# Counter_Display_v2.net
KiCad netlist of a schematic drawn in Altium Designer
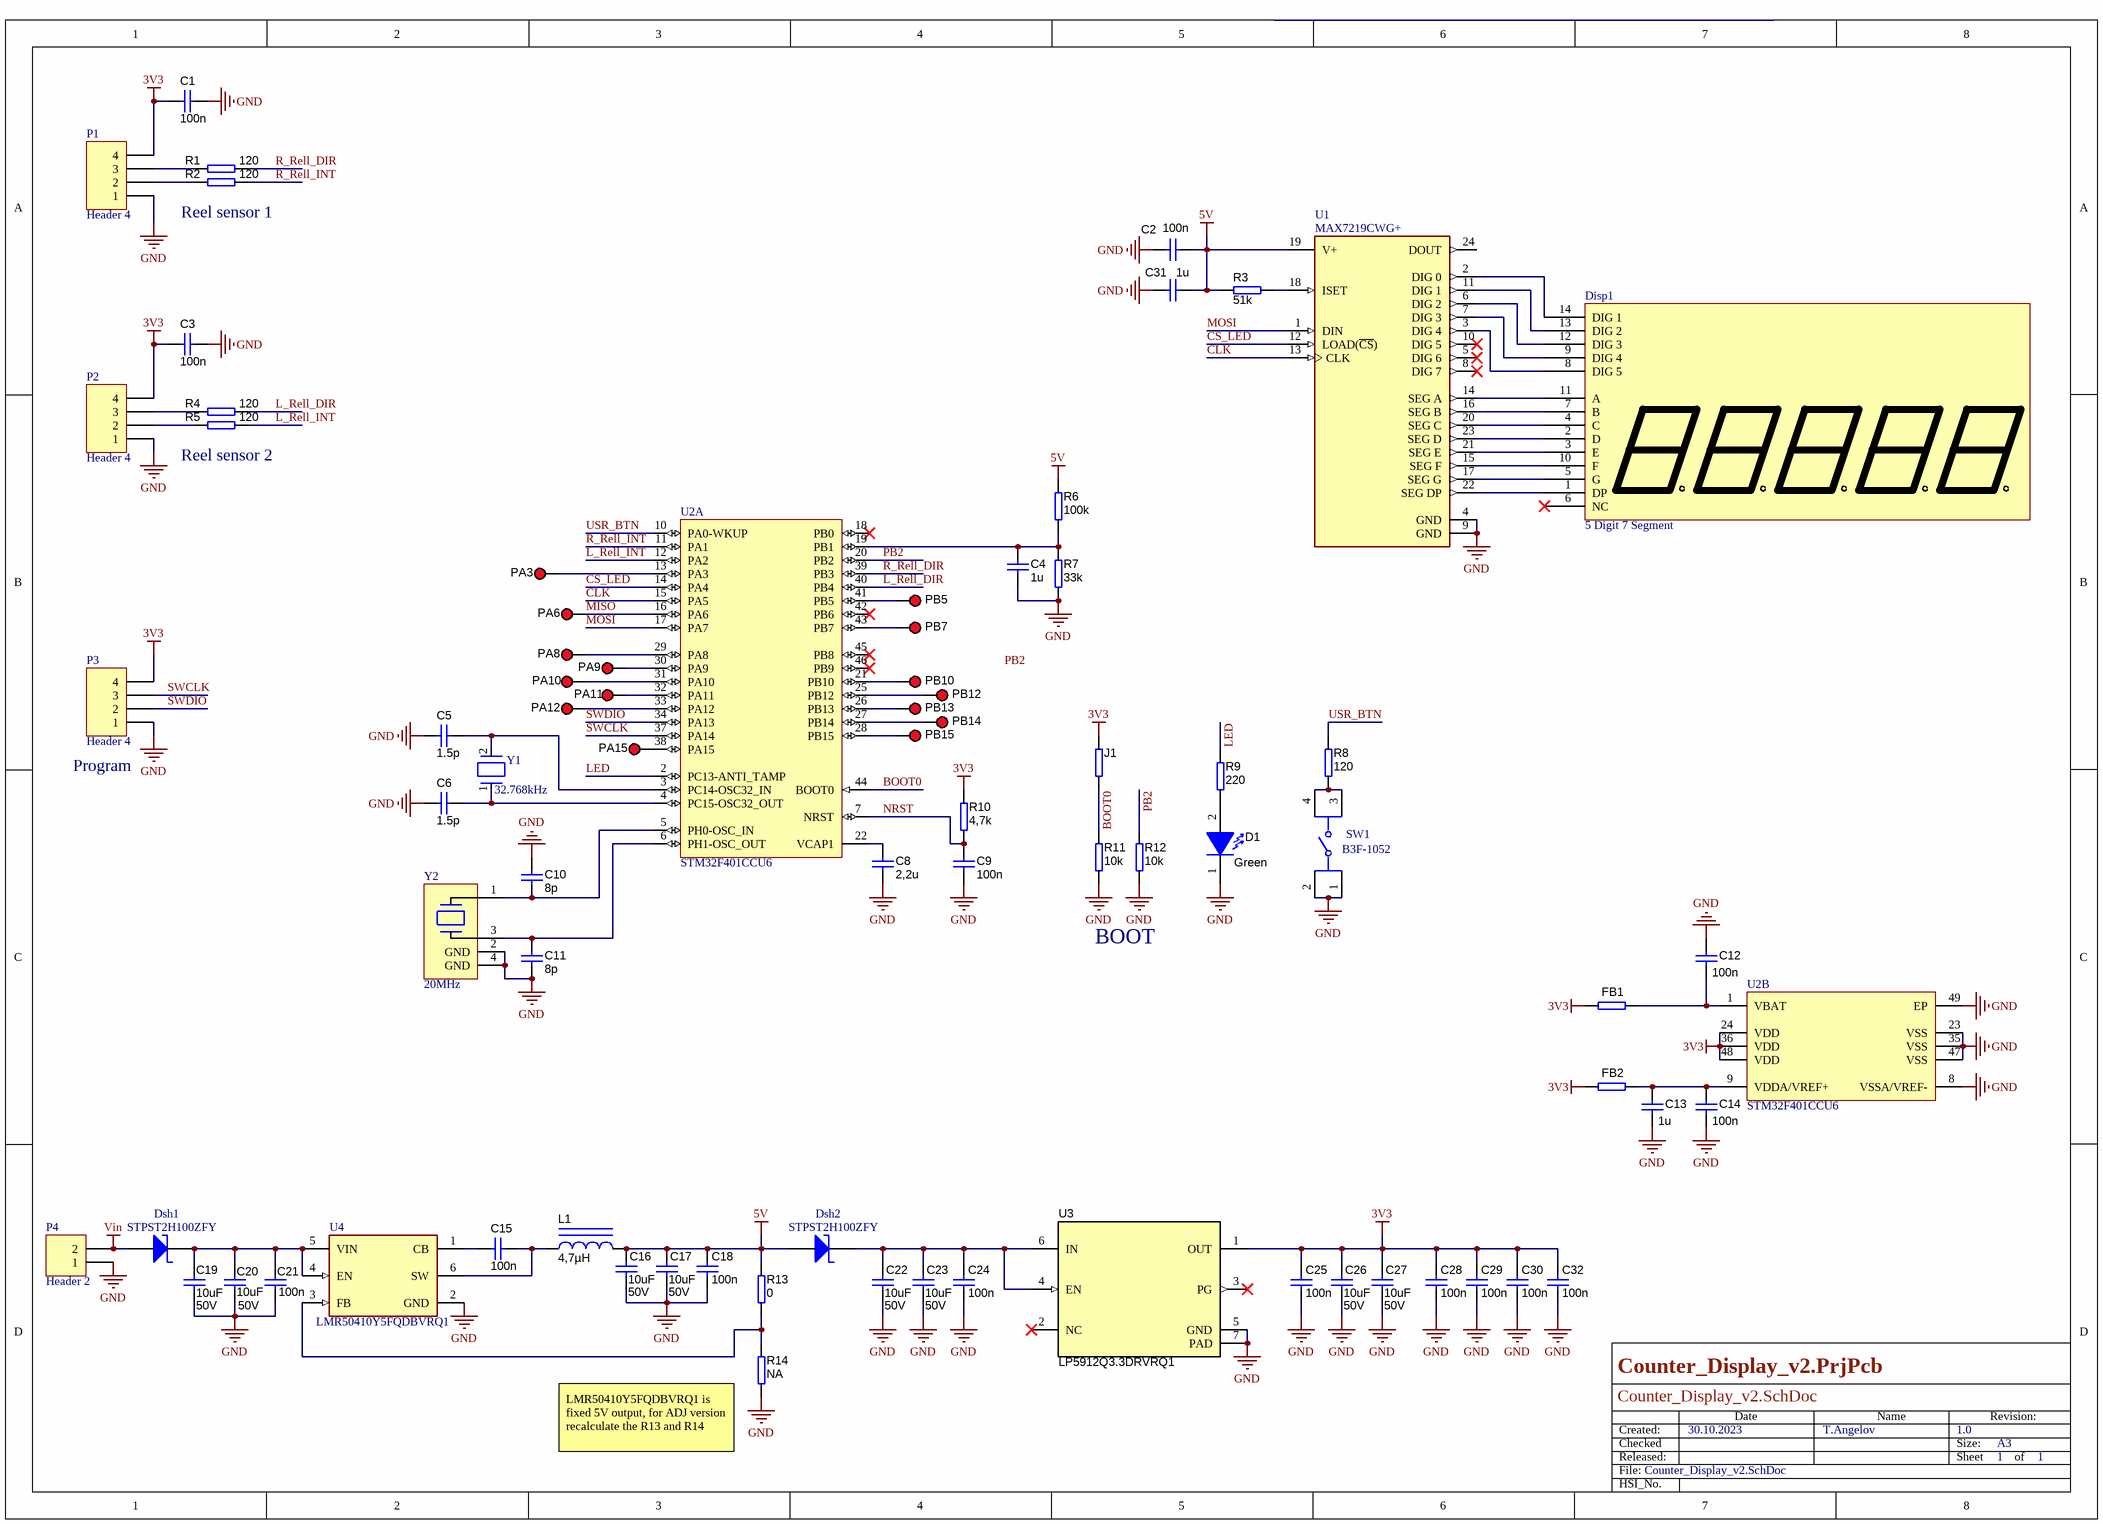
[diagram p0: Counter_Display_v2.SchDoc]

(export (version "E")
  (design (tool "Eeschema 10.0.6"))
  (components
    (comp (ref "C1")
      (value "100n")
      (footprint "0805_HV")
      (description "CAP, CERM, +/- 10%, X7S,  0805")
      (libsource (lib "Const_Cur_Source") (part "C0805"))
    )
    (comp (ref "C2")
      (value "100n")
      (footprint "0805_HV")
      (description "CAP, CERM, +/- 10%, X7S,  0805")
      (libsource (lib "Const_Cur_Source") (part "C0805"))
    )
    (comp (ref "C3")
      (value "100n")
      (footprint "0805_HV")
      (description "CAP, CERM, +/- 10%, X7S,  0805")
      (libsource (lib "Const_Cur_Source") (part "C0805"))
    )
    (comp (ref "C4")
      (value "1u")
      (footprint "0805_HV")
      (description "CAP, CERM, +/- 10%, X7S,  0805")
      (libsource (lib "Const_Cur_Source") (part "C0805"))
    )
    (comp (ref "C5")
      (value "1.5p")
      (footprint "0805_HV")
      (description "CAP, CERM, +/- 10%, X7S,  0805")
      (libsource (lib "Const_Cur_Source") (part "C0805"))
    )
    (comp (ref "C6")
      (value "1.5p")
      (footprint "0805_HV")
      (description "CAP, CERM, +/- 10%, X7S,  0805")
      (libsource (lib "Const_Cur_Source") (part "C0805"))
    )
    (comp (ref "C8")
      (value "2,2u")
      (footprint "0805_HV")
      (description "CAP, CERM, +/- 10%, X7S,  0805")
      (libsource (lib "Const_Cur_Source") (part "C0805"))
    )
    (comp (ref "C9")
      (value "100n")
      (footprint "0805_HV")
      (description "CAP, CERM, +/- 10%, X7S,  0805")
      (libsource (lib "Const_Cur_Source") (part "C0805"))
    )
    (comp (ref "C10")
      (value "8p")
      (footprint "0805_HV")
      (description "CAP, CERM, +/- 10%, X7S,  0805")
      (libsource (lib "Const_Cur_Source") (part "C0805"))
    )
    (comp (ref "C11")
      (value "8p")
      (footprint "0805_HV")
      (description "CAP, CERM, +/- 10%, X7S,  0805")
      (libsource (lib "Const_Cur_Source") (part "C0805"))
    )
    (comp (ref "C12")
      (value "100n")
      (footprint "0805_HV")
      (description "CAP, CERM, +/- 10%, X7S,  0805")
      (libsource (lib "Const_Cur_Source") (part "C0805"))
    )
    (comp (ref "C13")
      (value "1u")
      (footprint "0805_HV")
      (description "CAP, CERM, +/- 10%, X7S,  0805")
      (libsource (lib "Const_Cur_Source") (part "C0805"))
    )
    (comp (ref "C14")
      (value "100n")
      (footprint "0805_HV")
      (description "CAP, CERM, +/- 10%, X7S,  0805")
      (libsource (lib "Const_Cur_Source") (part "C0805"))
    )
    (comp (ref "C15")
      (value "100n")
      (footprint "0805_HV")
      (description "CAP, CERM, +/- 10%, X7S,  0805")
      (libsource (lib "Const_Cur_Source") (part "C0805"))
    )
    (comp (ref "C16")
      (value "10uF")
      (footprint "1206_180")
      (description "CAP, CERM, NP0, 1206")
      (fields (field (name "VALUE1") "50V"))
      (libsource (lib "Const_Cur_Source") (part "C1206"))
    )
    (comp (ref "C17")
      (value "10uF")
      (footprint "1206_180")
      (description "CAP, CERM, NP0, 1206")
      (fields (field (name "VALUE1") "50V"))
      (libsource (lib "Const_Cur_Source") (part "C1206"))
    )
    (comp (ref "C18")
      (value "100n")
      (footprint "0805_HV")
      (description "CAP, CERM, +/- 10%, X7S,  0805")
      (libsource (lib "Const_Cur_Source") (part "C0805"))
    )
    (comp (ref "C19")
      (value "10uF")
      (footprint "1206_180")
      (description "CAP, CERM, NP0, 1206")
      (fields (field (name "VALUE1") "50V"))
      (libsource (lib "Const_Cur_Source") (part "C1206"))
    )
    (comp (ref "C20")
      (value "10uF")
      (footprint "1206_180")
      (description "CAP, CERM, NP0, 1206")
      (fields (field (name "VALUE1") "50V"))
      (libsource (lib "Const_Cur_Source") (part "C1206"))
    )
    (comp (ref "C21")
      (value "100n")
      (footprint "0805_HV")
      (description "CAP, CERM, +/- 10%, X7S,  0805")
      (libsource (lib "Const_Cur_Source") (part "C0805"))
    )
    (comp (ref "C22")
      (value "10uF")
      (footprint "1206_180")
      (description "CAP, CERM, NP0, 1206")
      (fields (field (name "VALUE1") "50V"))
      (libsource (lib "Const_Cur_Source") (part "C1206"))
    )
    (comp (ref "C23")
      (value "10uF")
      (footprint "1206_180")
      (description "CAP, CERM, NP0, 1206")
      (fields (field (name "VALUE1") "50V"))
      (libsource (lib "Const_Cur_Source") (part "C1206"))
    )
    (comp (ref "C24")
      (value "100n")
      (footprint "0805_HV")
      (description "CAP, CERM, +/- 10%, X7S,  0805")
      (libsource (lib "Const_Cur_Source") (part "C0805"))
    )
    (comp (ref "C25")
      (value "100n")
      (footprint "0805_HV")
      (description "CAP, CERM, +/- 10%, X7S,  0805")
      (libsource (lib "Const_Cur_Source") (part "C0805"))
    )
    (comp (ref "C26")
      (value "10uF")
      (footprint "1206_180")
      (description "CAP, CERM, NP0, 1206")
      (fields (field (name "VALUE1") "50V"))
      (libsource (lib "Const_Cur_Source") (part "C1206"))
    )
    (comp (ref "C27")
      (value "10uF")
      (footprint "1206_180")
      (description "CAP, CERM, NP0, 1206")
      (fields (field (name "VALUE1") "50V"))
      (libsource (lib "Const_Cur_Source") (part "C1206"))
    )
    (comp (ref "C28")
      (value "100n")
      (footprint "0805_HV")
      (description "CAP, CERM, +/- 10%, X7S,  0805")
      (libsource (lib "Const_Cur_Source") (part "C0805"))
    )
    (comp (ref "C29")
      (value "100n")
      (footprint "0805_HV")
      (description "CAP, CERM, +/- 10%, X7S,  0805")
      (libsource (lib "Const_Cur_Source") (part "C0805"))
    )
    (comp (ref "C30")
      (value "100n")
      (footprint "0805_HV")
      (description "CAP, CERM, +/- 10%, X7S,  0805")
      (libsource (lib "Const_Cur_Source") (part "C0805"))
    )
    (comp (ref "C31")
      (value "1u")
      (footprint "0805_HV")
      (description "CAP, CERM, +/- 10%, X7S,  0805")
      (libsource (lib "Const_Cur_Source") (part "C0805"))
    )
    (comp (ref "C32")
      (value "100n")
      (footprint "0805_HV")
      (description "CAP, CERM, +/- 10%, X7S,  0805")
      (libsource (lib "Const_Cur_Source") (part "C0805"))
    )
    (comp (ref "D1")
      (value "Green")
      (footprint "WL-SMCW_GREEN")
      (description "LED, Green, SMD")
      (fields
        (field (name "MANUFACTURER") "Wurth Elektronik")
        (field (name "PARTNUMBER") "150060GS75000")
        (field (name "PUBLISHER") "Texas Instruments")
      )
      (libsource (lib "DCDC_SCH_Lib") (part "150060GS75000"))
    )
    (comp (ref "Disp1")
      (value "5 Digit 7 Segment")
      (footprint "5 Digit 7 Seg LED")
      (description "0,2\" 7 Segment LED 5 Digit Display")
      (libsource (lib "Const_Cur_Source") (part "5 Digit 7 Segment"))
    )
    (comp (ref "Dsh1")
      (value "STPST2H100ZFY")
      (footprint "ONSC-SOD-123-2-425-04_V")
      (description "Diode Shottky")
      (fields (field (name "Comment") "DIODE_Shottky"))
      (libsource (lib "Const_Cur_Source") (part "DIODE_Shottky"))
    )
    (comp (ref "Dsh2")
      (value "STPST2H100ZFY")
      (footprint "ONSC-SOD-123-2-425-04_V")
      (description "Diode Shottky")
      (fields (field (name "Comment") "DIODE_Shottky"))
      (libsource (lib "Const_Cur_Source") (part "DIODE_Shottky"))
    )
    (comp (ref "FB1")
      (value "~")
      (footprint "0805_HV")
      (description "RES, 1%, 0.1 W, 0805")
      (libsource (lib "Const_Cur_Source") (part "R0805"))
    )
    (comp (ref "FB2")
      (value "~")
      (footprint "0805_HV")
      (description "RES, 1%, 0.1 W, 0805")
      (libsource (lib "Const_Cur_Source") (part "R0805"))
    )
    (comp (ref "J1")
      (value "~")
      (footprint "0805_HV")
      (description "RES, 1%, 0.1 W, 0805")
      (libsource (lib "Const_Cur_Source") (part "R0805"))
    )
    (comp (ref "L1")
      (value "MSS5121-333MLB")
      (footprint "MSS5121")
      (description "Inductor, Shielded Drum Core, Ferrite, 33 µH, 0.67 A, 0.48 ohm, SMD")
      (fields
        (field (name "VALUEDISPLAYED") "4,7µH")
        (field (name "MANUFACTURER") "Coilcraft")
        (field (name "PUBLISHER") "Texas Instruments")
      )
      (libsource (lib "Inductor_Coilcraft") (part "MSS5121-333MLB"))
    )
    (comp (ref "P1")
      (value "Header 4")
      (footprint "4-Pol. Connector")
      (description "Header, 4-Pin")
      (fields (field (name "PUBLISHER") "Altium Limited"))
      (libsource (lib "Miscellaneous Connectors") (part "Header 4"))
    )
    (comp (ref "P2")
      (value "Header 4")
      (footprint "4-Pol. Connector")
      (description "Header, 4-Pin")
      (fields (field (name "PUBLISHER") "Altium Limited"))
      (libsource (lib "Miscellaneous Connectors") (part "Header 4"))
    )
    (comp (ref "P3")
      (value "Header 4")
      (footprint "HDR1X4")
      (description "Header, 4-Pin")
      (fields (field (name "PUBLISHER") "Altium Limited"))
      (libsource (lib "Miscellaneous Connectors") (part "Header 4"))
    )
    (comp (ref "P4")
      (value "Header 2")
      (footprint "HDR1X2")
      (description "Header, 2-Pin")
      (fields (field (name "PUBLISHER") "Altium Limited"))
      (libsource (lib "Miscellaneous Connectors") (part "Header 2"))
    )
    (comp (ref "PA3")
      (value "~")
      (footprint "TP")
      (description "Test Point, Miniature, Red, TH")
      (fields
        (field (name "PARTNUMBER") "5000")
        (field (name "MANUFACTURER") "Keystone")
        (field (name "PUBLISHER") "Texas Instruments")
      )
      (libsource (lib "Const_Cur_Source") (part "TP"))
    )
    (comp (ref "PA6")
      (value "~")
      (footprint "TP")
      (description "Test Point, Miniature, Red, TH")
      (fields
        (field (name "PARTNUMBER") "5000")
        (field (name "MANUFACTURER") "Keystone")
        (field (name "PUBLISHER") "Texas Instruments")
      )
      (libsource (lib "Const_Cur_Source") (part "TP"))
    )
    (comp (ref "PA8")
      (value "~")
      (footprint "TP")
      (description "Test Point, Miniature, Red, TH")
      (fields
        (field (name "PARTNUMBER") "5000")
        (field (name "MANUFACTURER") "Keystone")
        (field (name "PUBLISHER") "Texas Instruments")
      )
      (libsource (lib "Const_Cur_Source") (part "TP"))
    )
    (comp (ref "PA9")
      (value "~")
      (footprint "TP")
      (description "Test Point, Miniature, Red, TH")
      (fields
        (field (name "PARTNUMBER") "5000")
        (field (name "MANUFACTURER") "Keystone")
        (field (name "PUBLISHER") "Texas Instruments")
      )
      (libsource (lib "Const_Cur_Source") (part "TP"))
    )
    (comp (ref "PA10")
      (value "~")
      (footprint "TP")
      (description "Test Point, Miniature, Red, TH")
      (fields
        (field (name "PARTNUMBER") "5000")
        (field (name "MANUFACTURER") "Keystone")
        (field (name "PUBLISHER") "Texas Instruments")
      )
      (libsource (lib "Const_Cur_Source") (part "TP"))
    )
    (comp (ref "PA11")
      (value "~")
      (footprint "TP")
      (description "Test Point, Miniature, Red, TH")
      (fields
        (field (name "PARTNUMBER") "5000")
        (field (name "MANUFACTURER") "Keystone")
        (field (name "PUBLISHER") "Texas Instruments")
      )
      (libsource (lib "Const_Cur_Source") (part "TP"))
    )
    (comp (ref "PA12")
      (value "~")
      (footprint "TP")
      (description "Test Point, Miniature, Red, TH")
      (fields
        (field (name "PARTNUMBER") "5000")
        (field (name "MANUFACTURER") "Keystone")
        (field (name "PUBLISHER") "Texas Instruments")
      )
      (libsource (lib "Const_Cur_Source") (part "TP"))
    )
    (comp (ref "PA15")
      (value "~")
      (footprint "TP")
      (description "Test Point, Miniature, Red, TH")
      (fields
        (field (name "PARTNUMBER") "5000")
        (field (name "MANUFACTURER") "Keystone")
        (field (name "PUBLISHER") "Texas Instruments")
      )
      (libsource (lib "Const_Cur_Source") (part "TP"))
    )
    (comp (ref "PB5")
      (value "~")
      (footprint "TP")
      (description "Test Point, Miniature, Red, TH")
      (fields
        (field (name "PARTNUMBER") "5000")
        (field (name "MANUFACTURER") "Keystone")
        (field (name "PUBLISHER") "Texas Instruments")
      )
      (libsource (lib "Const_Cur_Source") (part "TP"))
    )
    (comp (ref "PB7")
      (value "~")
      (footprint "TP")
      (description "Test Point, Miniature, Red, TH")
      (fields
        (field (name "PARTNUMBER") "5000")
        (field (name "MANUFACTURER") "Keystone")
        (field (name "PUBLISHER") "Texas Instruments")
      )
      (libsource (lib "Const_Cur_Source") (part "TP"))
    )
    (comp (ref "PB10")
      (value "~")
      (footprint "TP")
      (description "Test Point, Miniature, Red, TH")
      (fields
        (field (name "PARTNUMBER") "5000")
        (field (name "MANUFACTURER") "Keystone")
        (field (name "PUBLISHER") "Texas Instruments")
      )
      (libsource (lib "Const_Cur_Source") (part "TP"))
    )
    (comp (ref "PB12")
      (value "~")
      (footprint "TP")
      (description "Test Point, Miniature, Red, TH")
      (fields
        (field (name "PARTNUMBER") "5000")
        (field (name "MANUFACTURER") "Keystone")
        (field (name "PUBLISHER") "Texas Instruments")
      )
      (libsource (lib "Const_Cur_Source") (part "TP"))
    )
    (comp (ref "PB13")
      (value "~")
      (footprint "TP")
      (description "Test Point, Miniature, Red, TH")
      (fields
        (field (name "PARTNUMBER") "5000")
        (field (name "MANUFACTURER") "Keystone")
        (field (name "PUBLISHER") "Texas Instruments")
      )
      (libsource (lib "Const_Cur_Source") (part "TP"))
    )
    (comp (ref "PB14")
      (value "~")
      (footprint "TP")
      (description "Test Point, Miniature, Red, TH")
      (fields
        (field (name "PARTNUMBER") "5000")
        (field (name "MANUFACTURER") "Keystone")
        (field (name "PUBLISHER") "Texas Instruments")
      )
      (libsource (lib "Const_Cur_Source") (part "TP"))
    )
    (comp (ref "PB15")
      (value "~")
      (footprint "TP")
      (description "Test Point, Miniature, Red, TH")
      (fields
        (field (name "PARTNUMBER") "5000")
        (field (name "MANUFACTURER") "Keystone")
        (field (name "PUBLISHER") "Texas Instruments")
      )
      (libsource (lib "Const_Cur_Source") (part "TP"))
    )
    (comp (ref "R1")
      (value "120")
      (footprint "0805_HV")
      (description "RES, 1%, 0.1 W, 0805")
      (libsource (lib "Const_Cur_Source") (part "R0805"))
    )
    (comp (ref "R2")
      (value "120")
      (footprint "0805_HV")
      (description "RES, 1%, 0.1 W, 0805")
      (libsource (lib "Const_Cur_Source") (part "R0805"))
    )
    (comp (ref "R3")
      (value "51k")
      (footprint "0805_HV")
      (description "RES, 1%, 0.1 W, 0805")
      (libsource (lib "Const_Cur_Source") (part "R0805"))
    )
    (comp (ref "R4")
      (value "120")
      (footprint "0805_HV")
      (description "RES, 1%, 0.1 W, 0805")
      (libsource (lib "Const_Cur_Source") (part "R0805"))
    )
    (comp (ref "R5")
      (value "120")
      (footprint "0805_HV")
      (description "RES, 1%, 0.1 W, 0805")
      (libsource (lib "Const_Cur_Source") (part "R0805"))
    )
    (comp (ref "R6")
      (value "100k")
      (footprint "0805_HV")
      (description "RES, 1%, 0.1 W, 0805")
      (libsource (lib "Const_Cur_Source") (part "R0805"))
    )
    (comp (ref "R7")
      (value "33k")
      (footprint "0805_HV")
      (description "RES, 1%, 0.1 W, 0805")
      (libsource (lib "Const_Cur_Source") (part "R0805"))
    )
    (comp (ref "R8")
      (value "120")
      (footprint "0805_HV")
      (description "RES, 1%, 0.1 W, 0805")
      (libsource (lib "Const_Cur_Source") (part "R0805"))
    )
    (comp (ref "R9")
      (value "220")
      (footprint "0805_HV")
      (description "RES, 1%, 0.1 W, 0805")
      (libsource (lib "Const_Cur_Source") (part "R0805"))
    )
    (comp (ref "R10")
      (value "4,7k")
      (footprint "0805_HV")
      (description "RES, 1%, 0.1 W, 0805")
      (libsource (lib "Const_Cur_Source") (part "R0805"))
    )
    (comp (ref "R11")
      (value "10k")
      (footprint "0805_HV")
      (description "RES, 1%, 0.1 W, 0805")
      (libsource (lib "Const_Cur_Source") (part "R0805"))
    )
    (comp (ref "R12")
      (value "10k")
      (footprint "0805_HV")
      (description "RES, 1%, 0.1 W, 0805")
      (libsource (lib "Const_Cur_Source") (part "R0805"))
    )
    (comp (ref "R13")
      (value "0")
      (footprint "0805_HV")
      (description "RES, 1%, 0.1 W, 0805")
      (libsource (lib "Const_Cur_Source") (part "R0805"))
    )
    (comp (ref "R14")
      (value "NA")
      (footprint "0805_HV")
      (description "RES, 1%, 0.1 W, 0805")
      (libsource (lib "Const_Cur_Source") (part "R0805"))
    )
    (comp (ref "SW1")
      (value "B3F-1052")
      (footprint "Omron_B3F-1052_0")
      (libsource (lib "Const_Cur_Source") (part "B3F-1052"))
    )
    (comp (ref "U1")
      (value "MAX7219CWG+")
      (footprint "Maxim_Integrated_W24-1_IPC_A")
      (libsource (lib "Const_Cur_Source") (part "MAX7219CWG+"))
    )
    (comp (ref "U2")
      (value "STM32F401CCU6")
      (footprint "STM-UFQFPN48_M")
      (fields (field (name "MANUFACTURER") "STMicroelectronics"))
      (libsource (lib "Const_Cur_Source") (part "STM32F401CCU6"))
    )
    (comp (ref "U3")
      (value "LP5912Q3.3DRVRQ1")
      (footprint "DRV0006A")
      (fields
        (field (name "ALTERNATE PARTNUMBER") "LP5912Q3.3DRVTQ1")
        (field (name "MANUFACTURER") "Texas Instruments")
        (field (name "SYMBOLCREATOR") "a0411947")
        (field (name "PUBLISHER") "Texas Instruments")
      )
      (libsource (lib "TI_Pre_Release1") (part "LP5912Q3.3DRVRQ1"))
    )
    (comp (ref "U4")
      (value "LMR50410Y5FQDBVRQ1")
      (footprint "Texas_Instruments_DBV0006A_IPC_A")
      (libsource (lib "Const_Cur_Source") (part "LMR50410Y5FQDBVRQ1"))
    )
    (comp (ref "Y1")
      (value "Qartz_32,768kHz")
      (footprint "Quartz_32.768kHz")
      (description "CRYS")
      (fields
        (field (name "MANUFACTURER") "Euroquartz")
        (field (name "OCTOPART PART NUMBER") "45978c55d5b29a50")
        (field (name "PART NUMBER") "32.768kHz")
      )
      (libsource (lib "Const_Cur_Source") (part "Qartz_32,768kHz"))
    )
    (comp (ref "Y2")
      (value "Qartz_20MHz")
      (footprint "Crystal Oscilator 25MHz")
      (description "CRYS")
      (fields
        (field (name "MANUFACTURER") "Euroquartz")
        (field (name "OCTOPART PART NUMBER") "45978c55d5b29a50")
        (field (name "PART NUMBER") "20MHz")
      )
      (libsource (lib "Const_Cur_Source") (part "Qartz_20MHz"))
    )
  )
  (nets
    (net (code "1") (name "/BOOT0") (class "Default")
      (node (ref "J1") (pin "1") (pinfunction "1_1") (pintype "passive"))
      (node (ref "R11") (pin "2") (pinfunction "2_2") (pintype "passive"))
      (node (ref "U2") (pin "44") (pinfunction "BOOT0_44") (pintype "input"))
    )
    (net (code "2") (name "/CLK") (class "Default")
      (node (ref "U1") (pin "13") (pinfunction "CLK_13") (pintype "input"))
      (node (ref "U2") (pin "15") (pinfunction "PA5_15") (pintype "bidirectional"))
    )
    (net (code "3") (name "/CS_LED") (class "Default")
      (node (ref "U1") (pin "12") (pinfunction "LOAD(~{CS})_12") (pintype "input"))
      (node (ref "U2") (pin "14") (pinfunction "PA4_14") (pintype "bidirectional"))
    )
    (net (code "4") (name "/LED") (class "Default")
      (node (ref "R9") (pin "2") (pinfunction "2_2") (pintype "passive"))
      (node (ref "U2") (pin "2") (pinfunction "PC13-ANTI_TAMP_2") (pintype "bidirectional"))
    )
    (net (code "5") (name "/L_Rell_DIR") (class "Default")
      (node (ref "R4") (pin "2") (pinfunction "2_2") (pintype "passive"))
      (node (ref "U2") (pin "40") (pinfunction "PB4_40") (pintype "bidirectional"))
    )
    (net (code "6") (name "/L_Rell_INT") (class "Default")
      (node (ref "R5") (pin "2") (pinfunction "2_2") (pintype "passive"))
      (node (ref "U2") (pin "12") (pinfunction "PA2_12") (pintype "bidirectional"))
    )
    (net (code "7") (name "/MISO") (class "Default")
      (node (ref "PA6") (pin "1") (pintype "passive"))
      (node (ref "U2") (pin "16") (pinfunction "PA6_16") (pintype "bidirectional"))
    )
    (net (code "8") (name "/MOSI") (class "Default")
      (node (ref "U1") (pin "1") (pinfunction "DIN_1") (pintype "input"))
      (node (ref "U2") (pin "17") (pinfunction "PA7_17") (pintype "bidirectional"))
    )
    (net (code "9") (name "/NRST") (class "Default")
      (node (ref "C9") (pin "2") (pinfunction "2_2") (pintype "passive"))
      (node (ref "R10") (pin "1") (pinfunction "1_1") (pintype "passive"))
      (node (ref "U2") (pin "7") (pinfunction "NRST_7") (pintype "bidirectional"))
    )
    (net (code "10") (name "/PB2") (class "Default")
      (node (ref "R12") (pin "2") (pinfunction "2_2") (pintype "passive"))
      (node (ref "U2") (pin "20") (pinfunction "PB2_20") (pintype "bidirectional"))
    )
    (net (code "11") (name "/R_Rell_DIR") (class "Default")
      (node (ref "R1") (pin "2") (pinfunction "2_2") (pintype "passive"))
      (node (ref "U2") (pin "39") (pinfunction "PB3_39") (pintype "bidirectional"))
    )
    (net (code "12") (name "/R_Rell_INT") (class "Default")
      (node (ref "R2") (pin "2") (pinfunction "2_2") (pintype "passive"))
      (node (ref "U2") (pin "11") (pinfunction "PA1_11") (pintype "bidirectional"))
    )
    (net (code "13") (name "/SWCLK") (class "Default")
      (node (ref "P3") (pin "3") (pinfunction "3_3") (pintype "passive"))
      (node (ref "U2") (pin "37") (pinfunction "PA14_37") (pintype "bidirectional"))
    )
    (net (code "14") (name "/SWDIO") (class "Default")
      (node (ref "P3") (pin "2") (pinfunction "2_2") (pintype "passive"))
      (node (ref "U2") (pin "34") (pinfunction "PA13_34") (pintype "bidirectional"))
    )
    (net (code "15") (name "/USR_BTN") (class "Default")
      (node (ref "R8") (pin "2") (pinfunction "2_2") (pintype "passive"))
      (node (ref "U2") (pin "10") (pinfunction "PA0-WKUP_10") (pintype "bidirectional"))
    )
    (net (code "16") (name "3V3") (class "Default")
      (node (ref "C1") (pin "1") (pinfunction "1_1") (pintype "passive"))
      (node (ref "C25") (pin "1") (pinfunction "1_1") (pintype "passive"))
      (node (ref "C26") (pin "1") (pinfunction "1_1") (pintype "passive"))
      (node (ref "C27") (pin "1") (pinfunction "1_1") (pintype "passive"))
      (node (ref "C28") (pin "1") (pinfunction "1_1") (pintype "passive"))
      (node (ref "C29") (pin "1") (pinfunction "1_1") (pintype "passive"))
      (node (ref "C3") (pin "1") (pinfunction "1_1") (pintype "passive"))
      (node (ref "C30") (pin "1") (pinfunction "1_1") (pintype "passive"))
      (node (ref "C32") (pin "1") (pinfunction "1_1") (pintype "passive"))
      (node (ref "FB1") (pin "2") (pinfunction "2_2") (pintype "passive"))
      (node (ref "FB2") (pin "2") (pinfunction "2_2") (pintype "passive"))
      (node (ref "J1") (pin "2") (pinfunction "2_2") (pintype "passive"))
      (node (ref "P1") (pin "4") (pinfunction "4_4") (pintype "passive"))
      (node (ref "P2") (pin "4") (pinfunction "4_4") (pintype "passive"))
      (node (ref "P3") (pin "4") (pinfunction "4_4") (pintype "passive"))
      (node (ref "R10") (pin "2") (pinfunction "2_2") (pintype "passive"))
      (node (ref "U2") (pin "24") (pinfunction "VDD_24") (pintype "power_in"))
      (node (ref "U2") (pin "36") (pinfunction "VDD_36") (pintype "power_in"))
      (node (ref "U2") (pin "48") (pinfunction "VDD_48") (pintype "power_in"))
      (node (ref "U3") (pin "1") (pinfunction "OUT_1") (pintype "power_in"))
    )
    (net (code "17") (name "5V") (class "Default")
      (node (ref "C16") (pin "1") (pinfunction "1_1") (pintype "passive"))
      (node (ref "C17") (pin "1") (pinfunction "1_1") (pintype "passive"))
      (node (ref "C18") (pin "1") (pinfunction "1_1") (pintype "passive"))
      (node (ref "C2") (pin "2") (pinfunction "2_2") (pintype "passive"))
      (node (ref "C31") (pin "2") (pinfunction "2_2") (pintype "passive"))
      (node (ref "Dsh2") (pin "A") (pinfunction "A_A") (pintype "passive"))
      (node (ref "L1") (pin "2") (pinfunction "2_2") (pintype "passive"))
      (node (ref "R13") (pin "1") (pinfunction "1_1") (pintype "passive"))
      (node (ref "R3") (pin "1") (pinfunction "1_1") (pintype "passive"))
      (node (ref "R6") (pin "1") (pinfunction "1_1") (pintype "passive"))
      (node (ref "U1") (pin "19") (pinfunction "V+_19") (pintype "power_in"))
    )
    (net (code "18") (name "GND") (class "Default")
      (node (ref "C1") (pin "2") (pinfunction "2_2") (pintype "passive"))
      (node (ref "C10") (pin "1") (pinfunction "1_1") (pintype "passive"))
      (node (ref "C11") (pin "2") (pinfunction "2_2") (pintype "passive"))
      (node (ref "C12") (pin "1") (pinfunction "1_1") (pintype "passive"))
      (node (ref "C13") (pin "2") (pinfunction "2_2") (pintype "passive"))
      (node (ref "C14") (pin "2") (pinfunction "2_2") (pintype "passive"))
      (node (ref "C16") (pin "2") (pinfunction "2_2") (pintype "passive"))
      (node (ref "C17") (pin "2") (pinfunction "2_2") (pintype "passive"))
      (node (ref "C18") (pin "2") (pinfunction "2_2") (pintype "passive"))
      (node (ref "C19") (pin "2") (pinfunction "2_2") (pintype "passive"))
      (node (ref "C2") (pin "1") (pinfunction "1_1") (pintype "passive"))
      (node (ref "C20") (pin "2") (pinfunction "2_2") (pintype "passive"))
      (node (ref "C21") (pin "2") (pinfunction "2_2") (pintype "passive"))
      (node (ref "C22") (pin "2") (pinfunction "2_2") (pintype "passive"))
      (node (ref "C23") (pin "2") (pinfunction "2_2") (pintype "passive"))
      (node (ref "C24") (pin "2") (pinfunction "2_2") (pintype "passive"))
      (node (ref "C25") (pin "2") (pinfunction "2_2") (pintype "passive"))
      (node (ref "C26") (pin "2") (pinfunction "2_2") (pintype "passive"))
      (node (ref "C27") (pin "2") (pinfunction "2_2") (pintype "passive"))
      (node (ref "C28") (pin "2") (pinfunction "2_2") (pintype "passive"))
      (node (ref "C29") (pin "2") (pinfunction "2_2") (pintype "passive"))
      (node (ref "C3") (pin "2") (pinfunction "2_2") (pintype "passive"))
      (node (ref "C30") (pin "2") (pinfunction "2_2") (pintype "passive"))
      (node (ref "C31") (pin "1") (pinfunction "1_1") (pintype "passive"))
      (node (ref "C32") (pin "2") (pinfunction "2_2") (pintype "passive"))
      (node (ref "C4") (pin "2") (pinfunction "2_2") (pintype "passive"))
      (node (ref "C5") (pin "1") (pinfunction "1_1") (pintype "passive"))
      (node (ref "C6") (pin "1") (pinfunction "1_1") (pintype "passive"))
      (node (ref "C8") (pin "2") (pinfunction "2_2") (pintype "passive"))
      (node (ref "C9") (pin "1") (pinfunction "1_1") (pintype "passive"))
      (node (ref "D1") (pin "1") (pinfunction "K_1") (pintype "passive"))
      (node (ref "P1") (pin "1") (pinfunction "1_1") (pintype "passive"))
      (node (ref "P2") (pin "1") (pinfunction "1_1") (pintype "passive"))
      (node (ref "P3") (pin "1") (pinfunction "1_1") (pintype "passive"))
      (node (ref "P4") (pin "1") (pinfunction "1_1") (pintype "passive"))
      (node (ref "R11") (pin "1") (pinfunction "1_1") (pintype "passive"))
      (node (ref "R12") (pin "1") (pinfunction "1_1") (pintype "passive"))
      (node (ref "R14") (pin "2") (pinfunction "2_2") (pintype "passive"))
      (node (ref "R7") (pin "2") (pinfunction "2_2") (pintype "passive"))
      (node (ref "SW1") (pin "1") (pinfunction "1_1") (pintype "passive"))
      (node (ref "SW1") (pin "2") (pinfunction "2_2") (pintype "passive"))
      (node (ref "U1") (pin "4") (pinfunction "GND_4") (pintype "power_in"))
      (node (ref "U1") (pin "9") (pinfunction "GND_9") (pintype "power_in"))
      (node (ref "U2") (pin "23") (pinfunction "VSS_23") (pintype "power_in"))
      (node (ref "U2") (pin "35") (pinfunction "VSS_35") (pintype "power_in"))
      (node (ref "U2") (pin "47") (pinfunction "VSS_47") (pintype "power_in"))
      (node (ref "U2") (pin "49") (pinfunction "EP_49") (pintype "power_in"))
      (node (ref "U2") (pin "8") (pinfunction "VSSA/VREF-_8") (pintype "power_in"))
      (node (ref "U3") (pin "5") (pinfunction "GND_5") (pintype "power_in"))
      (node (ref "U3") (pin "7") (pinfunction "PAD_7") (pintype "power_in"))
      (node (ref "U4") (pin "2") (pinfunction "GND_2") (pintype "power_in"))
      (node (ref "Y2") (pin "2") (pinfunction "GND_2") (pintype "passive"))
      (node (ref "Y2") (pin "4") (pinfunction "GND_4") (pintype "passive"))
    )
    (net (code "19") (name "Net-(D1-A)") (class "Default")
      (node (ref "D1") (pin "2") (pinfunction "A_2") (pintype "passive"))
      (node (ref "R9") (pin "1") (pinfunction "1_1") (pintype "passive"))
    )
    (net (code "20") (name "Net-(Disp1-A)") (class "Default")
      (node (ref "Disp1") (pin "11") (pinfunction "A_11") (pintype "passive"))
      (node (ref "U1") (pin "14") (pinfunction "SEG_A_14") (pintype "output"))
    )
    (net (code "21") (name "Net-(Disp1-B)") (class "Default")
      (node (ref "Disp1") (pin "7") (pinfunction "B_7") (pintype "passive"))
      (node (ref "U1") (pin "16") (pinfunction "SEG_B_16") (pintype "output"))
    )
    (net (code "22") (name "Net-(Disp1-C)") (class "Default")
      (node (ref "Disp1") (pin "4") (pinfunction "C_4") (pintype "passive"))
      (node (ref "U1") (pin "20") (pinfunction "SEG_C_20") (pintype "output"))
    )
    (net (code "23") (name "Net-(Disp1-D)") (class "Default")
      (node (ref "Disp1") (pin "2") (pinfunction "D_2") (pintype "passive"))
      (node (ref "U1") (pin "23") (pinfunction "SEG_D_23") (pintype "output"))
    )
    (net (code "24") (name "Net-(Disp1-DIG_1)") (class "Default")
      (node (ref "Disp1") (pin "14") (pinfunction "DIG_1_14") (pintype "passive"))
      (node (ref "U1") (pin "2") (pinfunction "DIG_0_2") (pintype "output"))
    )
    (net (code "25") (name "Net-(Disp1-DIG_2)") (class "Default")
      (node (ref "Disp1") (pin "13") (pinfunction "DIG_2_13") (pintype "passive"))
      (node (ref "U1") (pin "11") (pinfunction "DIG_1_11") (pintype "output"))
    )
    (net (code "26") (name "Net-(Disp1-DIG_3)") (class "Default")
      (node (ref "Disp1") (pin "12") (pinfunction "DIG_3_12") (pintype "passive"))
      (node (ref "U1") (pin "6") (pinfunction "DIG_2_6") (pintype "output"))
    )
    (net (code "27") (name "Net-(Disp1-DIG_4)") (class "Default")
      (node (ref "Disp1") (pin "9") (pinfunction "DIG_4_9") (pintype "passive"))
      (node (ref "U1") (pin "7") (pinfunction "DIG_3_7") (pintype "output"))
    )
    (net (code "28") (name "Net-(Disp1-DIG_5)") (class "Default")
      (node (ref "Disp1") (pin "8") (pinfunction "DIG_5_8") (pintype "passive"))
      (node (ref "U1") (pin "3") (pinfunction "DIG_4_3") (pintype "output"))
    )
    (net (code "29") (name "Net-(Disp1-DP)") (class "Default")
      (node (ref "Disp1") (pin "1") (pinfunction "DP_1") (pintype "passive"))
      (node (ref "U1") (pin "22") (pinfunction "SEG_DP_22") (pintype "output"))
    )
    (net (code "30") (name "Net-(Disp1-E)") (class "Default")
      (node (ref "Disp1") (pin "3") (pinfunction "E_3") (pintype "passive"))
      (node (ref "U1") (pin "21") (pinfunction "SEG_E_21") (pintype "output"))
    )
    (net (code "31") (name "Net-(Disp1-F)") (class "Default")
      (node (ref "Disp1") (pin "10") (pinfunction "F_10") (pintype "passive"))
      (node (ref "U1") (pin "15") (pinfunction "SEG_F_15") (pintype "output"))
    )
    (net (code "32") (name "Net-(Disp1-G)") (class "Default")
      (node (ref "Disp1") (pin "5") (pinfunction "G_5") (pintype "passive"))
      (node (ref "U1") (pin "17") (pinfunction "SEG_G_17") (pintype "output"))
    )
    (net (code "33") (name "Net-(P1-Pad2)") (class "Default")
      (node (ref "P1") (pin "2") (pinfunction "2_2") (pintype "passive"))
      (node (ref "R2") (pin "1") (pinfunction "1_1") (pintype "passive"))
    )
    (net (code "34") (name "Net-(P1-Pad3)") (class "Default")
      (node (ref "P1") (pin "3") (pinfunction "3_3") (pintype "passive"))
      (node (ref "R1") (pin "1") (pinfunction "1_1") (pintype "passive"))
    )
    (net (code "35") (name "Net-(P2-Pad2)") (class "Default")
      (node (ref "P2") (pin "2") (pinfunction "2_2") (pintype "passive"))
      (node (ref "R5") (pin "1") (pinfunction "1_1") (pintype "passive"))
    )
    (net (code "36") (name "Net-(P2-Pad3)") (class "Default")
      (node (ref "P2") (pin "3") (pinfunction "3_3") (pintype "passive"))
      (node (ref "R4") (pin "1") (pinfunction "1_1") (pintype "passive"))
    )
    (net (code "37") (name "Net-(R8-Pad1)") (class "Default")
      (node (ref "R8") (pin "1") (pinfunction "1_1") (pintype "passive"))
      (node (ref "SW1") (pin "3") (pinfunction "3_3") (pintype "passive"))
      (node (ref "SW1") (pin "4") (pinfunction "4_4") (pintype "passive"))
    )
    (net (code "38") (name "Net-(U1-ISET)") (class "Default")
      (node (ref "R3") (pin "2") (pinfunction "2_2") (pintype "passive"))
      (node (ref "U1") (pin "18") (pinfunction "ISET_18") (pintype "input"))
    )
    (net (code "39") (name "Net-(U2A-PA3)") (class "Default")
      (node (ref "PA3") (pin "1") (pintype "passive"))
      (node (ref "U2") (pin "13") (pinfunction "PA3_13") (pintype "bidirectional"))
    )
    (net (code "40") (name "Net-(U2A-PA8)") (class "Default")
      (node (ref "PA8") (pin "1") (pintype "passive"))
      (node (ref "U2") (pin "29") (pinfunction "PA8_29") (pintype "bidirectional"))
    )
    (net (code "41") (name "Net-(U2A-PA9)") (class "Default")
      (node (ref "PA9") (pin "1") (pintype "passive"))
      (node (ref "U2") (pin "30") (pinfunction "PA9_30") (pintype "bidirectional"))
    )
    (net (code "42") (name "Net-(U2A-PA10)") (class "Default")
      (node (ref "PA10") (pin "1") (pintype "passive"))
      (node (ref "U2") (pin "31") (pinfunction "PA10_31") (pintype "bidirectional"))
    )
    (net (code "43") (name "Net-(U2A-PA11)") (class "Default")
      (node (ref "PA11") (pin "1") (pintype "passive"))
      (node (ref "U2") (pin "32") (pinfunction "PA11_32") (pintype "bidirectional"))
    )
    (net (code "44") (name "Net-(U2A-PA12)") (class "Default")
      (node (ref "PA12") (pin "1") (pintype "passive"))
      (node (ref "U2") (pin "33") (pinfunction "PA12_33") (pintype "bidirectional"))
    )
    (net (code "45") (name "Net-(U2A-PA15)") (class "Default")
      (node (ref "PA15") (pin "1") (pintype "passive"))
      (node (ref "U2") (pin "38") (pinfunction "PA15_38") (pintype "bidirectional"))
    )
    (net (code "46") (name "Net-(U2A-PB1)") (class "Default")
      (node (ref "C4") (pin "1") (pinfunction "1_1") (pintype "passive"))
      (node (ref "R6") (pin "2") (pinfunction "2_2") (pintype "passive"))
      (node (ref "R7") (pin "1") (pinfunction "1_1") (pintype "passive"))
      (node (ref "U2") (pin "19") (pinfunction "PB1_19") (pintype "bidirectional"))
    )
    (net (code "47") (name "Net-(U2A-PB5)") (class "Default")
      (node (ref "PB5") (pin "1") (pintype "passive"))
      (node (ref "U2") (pin "41") (pinfunction "PB5_41") (pintype "bidirectional"))
    )
    (net (code "48") (name "Net-(U2A-PB7)") (class "Default")
      (node (ref "PB7") (pin "1") (pintype "passive"))
      (node (ref "U2") (pin "43") (pinfunction "PB7_43") (pintype "bidirectional"))
    )
    (net (code "49") (name "Net-(U2A-PB10)") (class "Default")
      (node (ref "PB10") (pin "1") (pintype "passive"))
      (node (ref "U2") (pin "21") (pinfunction "PB10_21") (pintype "bidirectional"))
    )
    (net (code "50") (name "Net-(U2A-PB12)") (class "Default")
      (node (ref "PB12") (pin "1") (pintype "passive"))
      (node (ref "U2") (pin "25") (pinfunction "PB12_25") (pintype "bidirectional"))
    )
    (net (code "51") (name "Net-(U2A-PB13)") (class "Default")
      (node (ref "PB13") (pin "1") (pintype "passive"))
      (node (ref "U2") (pin "26") (pinfunction "PB13_26") (pintype "bidirectional"))
    )
    (net (code "52") (name "Net-(U2A-PB14)") (class "Default")
      (node (ref "PB14") (pin "1") (pintype "passive"))
      (node (ref "U2") (pin "27") (pinfunction "PB14_27") (pintype "bidirectional"))
    )
    (net (code "53") (name "Net-(U2A-PB15)") (class "Default")
      (node (ref "PB15") (pin "1") (pintype "passive"))
      (node (ref "U2") (pin "28") (pinfunction "PB15_28") (pintype "bidirectional"))
    )
    (net (code "54") (name "Net-(U2A-PC14-OSC32_IN)") (class "Default")
      (node (ref "C5") (pin "2") (pinfunction "2_2") (pintype "passive"))
      (node (ref "U2") (pin "3") (pinfunction "PC14-OSC32_IN_3") (pintype "bidirectional"))
      (node (ref "Y1") (pin "2") (pinfunction "2_2") (pintype "passive"))
    )
    (net (code "55") (name "Net-(U2A-PC15-OSC32_OUT)") (class "Default")
      (node (ref "C6") (pin "2") (pinfunction "2_2") (pintype "passive"))
      (node (ref "U2") (pin "4") (pinfunction "PC15-OSC32_OUT_4") (pintype "bidirectional"))
      (node (ref "Y1") (pin "1") (pinfunction "1_1") (pintype "passive"))
    )
    (net (code "56") (name "Net-(U2A-PH0-OSC_IN)") (class "Default")
      (node (ref "C10") (pin "2") (pinfunction "2_2") (pintype "passive"))
      (node (ref "U2") (pin "5") (pinfunction "PH0-OSC_IN_5") (pintype "bidirectional"))
      (node (ref "Y2") (pin "1") (pintype "passive"))
    )
    (net (code "57") (name "Net-(U2A-PH1-OSC_OUT)") (class "Default")
      (node (ref "C11") (pin "1") (pinfunction "1_1") (pintype "passive"))
      (node (ref "U2") (pin "6") (pinfunction "PH1-OSC_OUT_6") (pintype "bidirectional"))
      (node (ref "Y2") (pin "3") (pintype "passive"))
    )
    (net (code "58") (name "Net-(U2A-VCAP1)") (class "Default")
      (node (ref "C8") (pin "1") (pinfunction "1_1") (pintype "passive"))
      (node (ref "U2") (pin "22") (pinfunction "VCAP1_22") (pintype "power_in"))
    )
    (net (code "59") (name "Net-(U2B-VBAT)") (class "Default")
      (node (ref "C12") (pin "2") (pinfunction "2_2") (pintype "passive"))
      (node (ref "FB1") (pin "1") (pinfunction "1_1") (pintype "passive"))
      (node (ref "U2") (pin "1") (pinfunction "VBAT_1") (pintype "power_in"))
    )
    (net (code "60") (name "Net-(U2B-VDDA{slash}VREF+)") (class "Default")
      (node (ref "C13") (pin "1") (pinfunction "1_1") (pintype "passive"))
      (node (ref "C14") (pin "1") (pinfunction "1_1") (pintype "passive"))
      (node (ref "FB2") (pin "1") (pinfunction "1_1") (pintype "passive"))
      (node (ref "U2") (pin "9") (pinfunction "VDDA/VREF+_9") (pintype "power_in"))
    )
    (net (code "61") (name "Net-(U3-EN)") (class "Default")
      (node (ref "C22") (pin "1") (pinfunction "1_1") (pintype "passive"))
      (node (ref "C23") (pin "1") (pinfunction "1_1") (pintype "passive"))
      (node (ref "C24") (pin "1") (pinfunction "1_1") (pintype "passive"))
      (node (ref "Dsh2") (pin "K") (pinfunction "K_K") (pintype "passive"))
      (node (ref "U3") (pin "4") (pinfunction "EN_4") (pintype "input"))
      (node (ref "U3") (pin "6") (pinfunction "IN_6") (pintype "power_in"))
    )
    (net (code "62") (name "Net-(U4-CB)") (class "Default")
      (node (ref "C15") (pin "1") (pinfunction "1_1") (pintype "passive"))
      (node (ref "U4") (pin "1") (pinfunction "CB_1") (pintype "passive"))
    )
    (net (code "63") (name "Net-(U4-EN)") (class "Default")
      (node (ref "C19") (pin "1") (pinfunction "1_1") (pintype "passive"))
      (node (ref "C20") (pin "1") (pinfunction "1_1") (pintype "passive"))
      (node (ref "C21") (pin "1") (pinfunction "1_1") (pintype "passive"))
      (node (ref "Dsh1") (pin "K") (pinfunction "K_K") (pintype "passive"))
      (node (ref "U4") (pin "4") (pinfunction "EN_4") (pintype "input"))
      (node (ref "U4") (pin "5") (pinfunction "VIN_5") (pintype "power_in"))
    )
    (net (code "64") (name "Net-(U4-FB)") (class "Default")
      (node (ref "R13") (pin "2") (pinfunction "2_2") (pintype "passive"))
      (node (ref "R14") (pin "1") (pinfunction "1_1") (pintype "passive"))
      (node (ref "U4") (pin "3") (pinfunction "FB_3") (pintype "input"))
    )
    (net (code "65") (name "Net-(U4-SW)") (class "Default")
      (node (ref "C15") (pin "2") (pinfunction "2_2") (pintype "passive"))
      (node (ref "L1") (pin "1") (pinfunction "1_1") (pintype "passive"))
      (node (ref "U4") (pin "6") (pinfunction "SW_6") (pintype "passive"))
    )
    (net (code "66") (name "Vin") (class "Default")
      (node (ref "Dsh1") (pin "A") (pinfunction "A_A") (pintype "passive"))
      (node (ref "P4") (pin "2") (pinfunction "2_2") (pintype "passive"))
    )
    (net (code "67") (name "unconnected-(Disp1-NC-Pad6)") (class "Default")
      (node (ref "Disp1") (pin "6") (pinfunction "NC_6") (pintype "passive+no_connect"))
    )
    (net (code "68") (name "unconnected-(U1-DIG_5-Pad10)") (class "Default")
      (node (ref "U1") (pin "10") (pinfunction "DIG_5_10") (pintype "output+no_connect"))
    )
    (net (code "69") (name "unconnected-(U1-DIG_6-Pad5)") (class "Default")
      (node (ref "U1") (pin "5") (pinfunction "DIG_6_5") (pintype "output+no_connect"))
    )
    (net (code "70") (name "unconnected-(U1-DIG_7-Pad8)") (class "Default")
      (node (ref "U1") (pin "8") (pinfunction "DIG_7_8") (pintype "output+no_connect"))
    )
    (net (code "71") (name "unconnected-(U1-DOUT-Pad24)") (class "Default")
      (node (ref "U1") (pin "24") (pinfunction "DOUT_24") (pintype "output"))
    )
    (net (code "72") (name "unconnected-(U2A-PB0-Pad18)") (class "Default")
      (node (ref "U2") (pin "18") (pinfunction "PB0_18") (pintype "bidirectional+no_connect"))
    )
    (net (code "73") (name "unconnected-(U2A-PB6-Pad42)") (class "Default")
      (node (ref "U2") (pin "42") (pinfunction "PB6_42") (pintype "bidirectional+no_connect"))
    )
    (net (code "74") (name "unconnected-(U2A-PB8-Pad45)") (class "Default")
      (node (ref "U2") (pin "45") (pinfunction "PB8_45") (pintype "bidirectional+no_connect"))
    )
    (net (code "75") (name "unconnected-(U2A-PB9-Pad46)") (class "Default")
      (node (ref "U2") (pin "46") (pinfunction "PB9_46") (pintype "bidirectional+no_connect"))
    )
    (net (code "76") (name "unconnected-(U3-NC-Pad2)") (class "Default")
      (node (ref "U3") (pin "2") (pinfunction "NC_2") (pintype "passive+no_connect"))
    )
    (net (code "77") (name "unconnected-(U3-PG-Pad3)") (class "Default")
      (node (ref "U3") (pin "3") (pinfunction "PG_3") (pintype "output+no_connect"))
    )
  )
)
